# StLink.net
KiCad netlist of a schematic drawn in Altium Designer
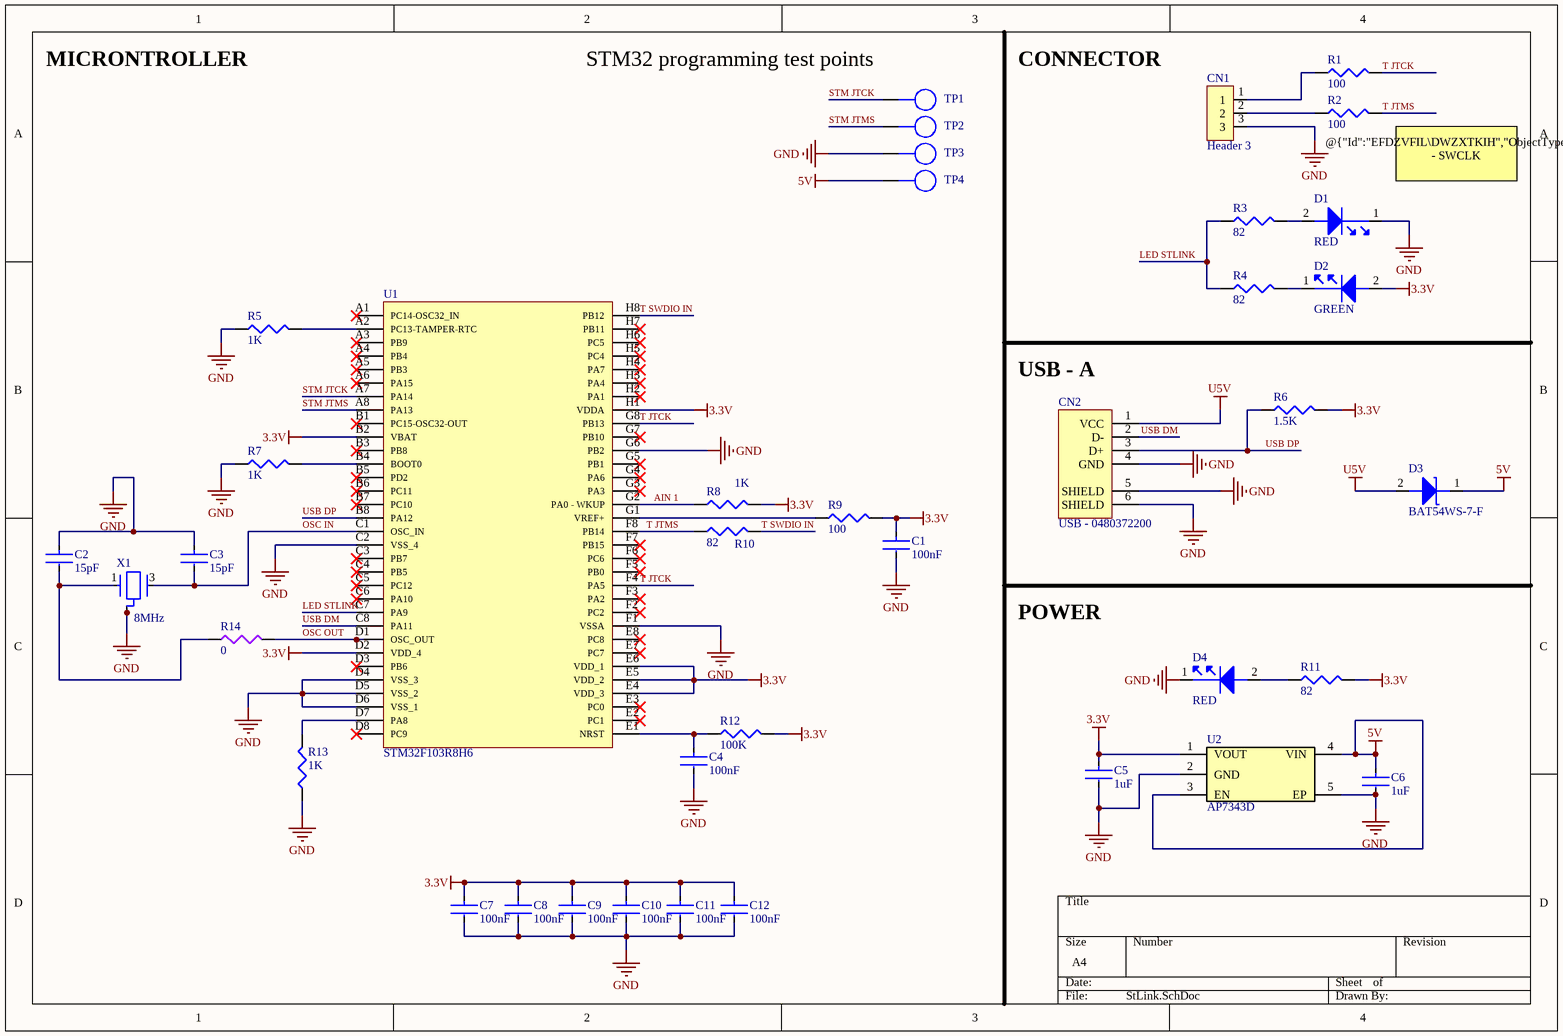
[diagram p0: StLink.SchDoc]

(export (version "E")
  (design (tool "Eeschema 10.0.6"))
  (components
    (comp (ref "C1")
      (value "100nF")
      (footprint "C0201")
      (description "6.3V 100nF X5R ±10% 0201 Multilayer Ceramic Capacitors MLCC - SMD/SMT ROHS")
      (fields
        (field (name "MANUFACTURER") "Murata")
        (field (name "MANUFACTURER PART NUMBER") "GRM033R60J104KE19D")
      )
      (libsource (lib "StLink") (part "GRM033R60J104KE19D"))
    )
    (comp (ref "C2")
      (value "15pF")
      (footprint "C0201")
      (description "25V 15pF C0G ±5% 0201 Multilayer Ceramic Capacitors MLCC - SMD/SMT ROHS")
      (fields
        (field (name "MANUFACTURER") "Murata")
        (field (name "MANUFACTURER PART NUMBER") "GRM0335C1E150JA01D")
      )
      (libsource (lib "StLink") (part "GRM0335C1E150JA01D"))
    )
    (comp (ref "C3")
      (value "15pF")
      (footprint "C0201")
      (description "25V 15pF C0G ±5% 0201 Multilayer Ceramic Capacitors MLCC - SMD/SMT ROHS")
      (fields
        (field (name "MANUFACTURER") "Murata")
        (field (name "MANUFACTURER PART NUMBER") "GRM0335C1E150JA01D")
      )
      (libsource (lib "StLink") (part "GRM0335C1E150JA01D"))
    )
    (comp (ref "C4")
      (value "100nF")
      (footprint "C0201")
      (description "6.3V 100nF X5R ±10% 0201 Multilayer Ceramic Capacitors MLCC - SMD/SMT ROHS")
      (fields
        (field (name "MANUFACTURER") "Murata")
        (field (name "MANUFACTURER PART NUMBER") "GRM033R60J104KE19D")
      )
      (libsource (lib "StLink") (part "GRM033R60J104KE19D"))
    )
    (comp (ref "C5")
      (value "1uF")
      (footprint "C0201")
      (description "16V 1uF X5R ±20% 0201 Multilayer Ceramic Capacitors MLCC - SMD/SMT ROHS")
      (fields
        (field (name "MANUFACTURER") "Murata")
        (field (name "MANUFACTURER PART NUMBER") "GRM033R61C105ME15D")
      )
      (libsource (lib "StLink") (part "GRM033R61C105ME15D"))
    )
    (comp (ref "C6")
      (value "1uF")
      (footprint "C0201")
      (description "16V 1uF X5R ±20% 0201 Multilayer Ceramic Capacitors MLCC - SMD/SMT ROHS")
      (fields
        (field (name "MANUFACTURER") "Murata")
        (field (name "MANUFACTURER PART NUMBER") "GRM033R61C105ME15D")
      )
      (libsource (lib "StLink") (part "GRM033R61C105ME15D"))
    )
    (comp (ref "C7")
      (value "100nF")
      (footprint "C0201")
      (description "6.3V 100nF X5R ±10% 0201 Multilayer Ceramic Capacitors MLCC - SMD/SMT ROHS")
      (fields
        (field (name "MANUFACTURER") "Murata")
        (field (name "MANUFACTURER PART NUMBER") "GRM033R60J104KE19D")
      )
      (libsource (lib "StLink") (part "GRM033R60J104KE19D"))
    )
    (comp (ref "C8")
      (value "100nF")
      (footprint "C0201")
      (description "6.3V 100nF X5R ±10% 0201 Multilayer Ceramic Capacitors MLCC - SMD/SMT ROHS")
      (fields
        (field (name "MANUFACTURER") "Murata")
        (field (name "MANUFACTURER PART NUMBER") "GRM033R60J104KE19D")
      )
      (libsource (lib "StLink") (part "GRM033R60J104KE19D"))
    )
    (comp (ref "C9")
      (value "100nF")
      (footprint "C0201")
      (description "6.3V 100nF X5R ±10% 0201 Multilayer Ceramic Capacitors MLCC - SMD/SMT ROHS")
      (fields
        (field (name "MANUFACTURER") "Murata")
        (field (name "MANUFACTURER PART NUMBER") "GRM033R60J104KE19D")
      )
      (libsource (lib "StLink") (part "GRM033R60J104KE19D"))
    )
    (comp (ref "C10")
      (value "100nF")
      (footprint "C0201")
      (description "6.3V 100nF X5R ±10% 0201 Multilayer Ceramic Capacitors MLCC - SMD/SMT ROHS")
      (fields
        (field (name "MANUFACTURER") "Murata")
        (field (name "MANUFACTURER PART NUMBER") "GRM033R60J104KE19D")
      )
      (libsource (lib "StLink") (part "GRM033R60J104KE19D"))
    )
    (comp (ref "C11")
      (value "100nF")
      (footprint "C0201")
      (description "6.3V 100nF X5R ±10% 0201 Multilayer Ceramic Capacitors MLCC - SMD/SMT ROHS")
      (fields
        (field (name "MANUFACTURER") "Murata")
        (field (name "MANUFACTURER PART NUMBER") "GRM033R60J104KE19D")
      )
      (libsource (lib "StLink") (part "GRM033R60J104KE19D"))
    )
    (comp (ref "C12")
      (value "100nF")
      (footprint "C0201")
      (description "6.3V 100nF X5R ±10% 0201 Multilayer Ceramic Capacitors MLCC - SMD/SMT ROHS")
      (fields
        (field (name "MANUFACTURER") "Murata")
        (field (name "MANUFACTURER PART NUMBER") "GRM033R60J104KE19D")
      )
      (libsource (lib "StLink") (part "GRM033R60J104KE19D"))
    )
    (comp (ref "CN1")
      (value "Header 3")
      (footprint "H3x1")
      (description "Conn Shrouded Header (4 Sides) HDR 3 POS 1mm Solder RA Side Entry SMD Micro Mate™ Bulk")
      (fields
        (field (name "MANUFACTURER") "Samtec")
        (field (name "MANUFACTURER PART NUMBER") "T1M-03-F-SH-L")
      )
      (libsource (lib "StLink") (part "T1M-03-F-SH-L"))
    )
    (comp (ref "CN2")
      (value "USB - 0480372200")
      (footprint "usb A")
      (description "USB Connector, 4 Contact(s), Male, Right Angle, Surface Mount Terminal, Locking, Plug")
      (fields (field (name "MANUFACTURER") "Molex") (field (name "MANUFACTURER PART NUMBER") "48037-2200"))
      (libsource (lib "StLink") (part "48037-2200"))
    )
    (comp (ref "D1")
      (value "RED")
      (footprint "Led 0402")
      (description "Wurth Elektronik LED, WL-SMCC, 1005 (0402), 625 nm, 1 x 0.5 x 0.4mm")
      (fields
        (field (name "MANUFACTURER") "Wurth Elektronik")
        (field (name "MANUFACTURER PART NUMBER") "150040RS73240")
      )
      (libsource (lib "StLink") (part "150040RS73240"))
    )
    (comp (ref "D2")
      (value "GREEN")
      (footprint "Led 0402")
      (description "Wurth Elektronik LED, WL-SMCC, 1005 (0402), 570 nm, 1 x 0.5 x 0.4mm")
      (fields
        (field (name "MANUFACTURER") "Wurth Elektronik")
        (field (name "MANUFACTURER PART NUMBER") "150040VS73240")
      )
      (libsource (lib "StLink") (part "150040VS73240"))
    )
    (comp (ref "D3")
      (value "BAT54WS-7-F")
      (footprint "SOD323")
      (description "Schottky Diode Sod323 T&r 3K Rohs Compliant: Yes ¦Diodes Inc. BAT54WS-7-F")
      (fields (field (name "MANUFACTURER") "Diodes Inc."))
      (libsource (lib "StLink") (part "BAT54WS-7-F"))
    )
    (comp (ref "D4")
      (value "RED")
      (footprint "Led 0402")
      (description "Wurth Elektronik LED, WL-SMCC, 1005 (0402), 625 nm, 1 x 0.5 x 0.4mm")
      (fields
        (field (name "MANUFACTURER") "Wurth Elektronik")
        (field (name "MANUFACTURER PART NUMBER") "150040RS73240")
      )
      (libsource (lib "StLink") (part "150040RS73240"))
    )
    (comp (ref "R1")
      (value "100")
      (footprint "R0201")
      (description "50mW Thick Film Resistors 25V ±1% ±200ppm/℃ 100Ω 0201 Chip Resistor - Surface Mount ROHS")
      (fields
        (field (name "MANUFACTURER") "Yageo Group")
        (field (name "MANUFACTURER PART NUMBER") "RC0201FR-07100RL")
      )
      (libsource (lib "StLink") (part "RC0201FR-07100RL"))
    )
    (comp (ref "R2")
      (value "100")
      (footprint "R0201")
      (description "50mW Thick Film Resistors 25V ±1% ±200ppm/℃ 100Ω 0201 Chip Resistor - Surface Mount ROHS")
      (fields
        (field (name "MANUFACTURER") "Yageo Group")
        (field (name "MANUFACTURER PART NUMBER") "RC0201FR-07100RL")
      )
      (libsource (lib "StLink") (part "RC0201FR-07100RL"))
    )
    (comp (ref "R3")
      (value "82")
      (footprint "R0201")
      (description "Res Thick Film 0201 82 Ohm 5% 0.05W(1/20W) ±200ppm/C Pad SMD T/R")
      (fields
        (field (name "MANUFACTURER") "Yageo Group")
        (field (name "MANUFACTURER PART NUMBER") "RC0201JR-0782RL")
      )
      (libsource (lib "StLink") (part "RC0201JR-0782RL"))
    )
    (comp (ref "R4")
      (value "82")
      (footprint "R0201")
      (description "Res Thick Film 0201 82 Ohm 5% 0.05W(1/20W) ±200ppm/C Pad SMD T/R")
      (fields
        (field (name "MANUFACTURER") "Yageo Group")
        (field (name "MANUFACTURER PART NUMBER") "RC0201JR-0782RL")
      )
      (libsource (lib "StLink") (part "RC0201JR-0782RL"))
    )
    (comp (ref "R5")
      (value "1K")
      (footprint "R0201")
      (description "Res Thick Film 0201 1K Ohm 1% 0.05W(1/20W) ±200ppm/C Pad SMD T/R")
      (fields
        (field (name "MANUFACTURER") "Yageo Group")
        (field (name "MANUFACTURER PART NUMBER") "RC0201FR-071KL")
      )
      (libsource (lib "StLink") (part "RC0201FR-071KL"))
    )
    (comp (ref "R6")
      (value "1.5K")
      (footprint "R0201")
      (description "Res Thick Film 0201 1.5K Ohm 5% 0.05W(1/20W) ±200ppm/C Pad SMD T/R")
      (fields
        (field (name "MANUFACTURER") "Yageo Group")
        (field (name "MANUFACTURER PART NUMBER") "RC0201JR-071K5L")
      )
      (libsource (lib "StLink") (part "RC0201JR-071K5L"))
    )
    (comp (ref "R7")
      (value "1K")
      (footprint "R0201")
      (description "Res Thick Film 0201 1K Ohm 1% 0.05W(1/20W) ±200ppm/C Pad SMD T/R")
      (fields
        (field (name "MANUFACTURER") "Yageo Group")
        (field (name "MANUFACTURER PART NUMBER") "RC0201FR-071KL")
      )
      (libsource (lib "StLink") (part "RC0201FR-071KL"))
    )
    (comp (ref "R8")
      (value "1K")
      (footprint "R0201")
      (description "Res Thick Film 0201 1K Ohm 1% 0.05W(1/20W) ±200ppm/C Pad SMD T/R")
      (fields
        (field (name "MANUFACTURER") "Yageo Group")
        (field (name "MANUFACTURER PART NUMBER") "RC0201FR-071KL")
      )
      (libsource (lib "StLink") (part "RC0201FR-071KL"))
    )
    (comp (ref "R9")
      (value "100")
      (footprint "R0201")
      (description "50mW Thick Film Resistors 25V ±1% ±200ppm/℃ 100Ω 0201 Chip Resistor - Surface Mount ROHS")
      (fields
        (field (name "MANUFACTURER") "Yageo Group")
        (field (name "MANUFACTURER PART NUMBER") "RC0201FR-07100RL")
      )
      (libsource (lib "StLink") (part "RC0201FR-07100RL"))
    )
    (comp (ref "R10")
      (value "82")
      (footprint "R0201")
      (description "Res Thick Film 0201 82 Ohm 5% 0.05W(1/20W) ±200ppm/C Pad SMD T/R")
      (fields
        (field (name "MANUFACTURER") "Yageo Group")
        (field (name "MANUFACTURER PART NUMBER") "RC0201JR-0782RL")
      )
      (libsource (lib "StLink") (part "RC0201JR-0782RL"))
    )
    (comp (ref "R11")
      (value "82")
      (footprint "R0201")
      (description "Res Thick Film 0201 82 Ohm 5% 0.05W(1/20W) ±200ppm/C Pad SMD T/R")
      (fields
        (field (name "MANUFACTURER") "Yageo Group")
        (field (name "MANUFACTURER PART NUMBER") "RC0201JR-0782RL")
      )
      (libsource (lib "StLink") (part "RC0201JR-0782RL"))
    )
    (comp (ref "R12")
      (value "100K")
      (footprint "R0201")
      (description "50mW Thick Film Resistors 25V ±1% ±200ppm/℃ 100kΩ 0201 Chip Resistor - Surface Mount ROHS")
      (fields
        (field (name "MANUFACTURER") "Yageo Group")
        (field (name "MANUFACTURER PART NUMBER") "RC0201FR-07100KL")
      )
      (libsource (lib "StLink") (part "RC0201FR-07100KL"))
    )
    (comp (ref "R13")
      (value "1K")
      (footprint "R0201")
      (description "Res Thick Film 0201 1K Ohm 1% 0.05W(1/20W) ±200ppm/C Pad SMD T/R")
      (fields
        (field (name "MANUFACTURER") "Yageo Group")
        (field (name "MANUFACTURER PART NUMBER") "RC0201FR-071KL")
      )
      (libsource (lib "StLink") (part "RC0201FR-071KL"))
    )
    (comp (ref "R14")
      (value "0")
      (footprint "R0201")
      (description "GENERAL PURPOSE CHIP RESISTOR Metal Glaze/thick Film, 0.05W, 0ohm, Surface Mount, 0201")
      (fields
        (field (name "MANUFACTURER") "Yageo Group")
        (field (name "MANUFACTURER PART NUMBER") "RC0201JR-070RL")
      )
      (libsource (lib "StLink") (part "RC0201JR-070RL"))
    )
    (comp (ref "TP1") (value "Test_Point") (footprint "PAD") (libsource (lib "StLink") (part "Test_Point")))
    (comp (ref "TP2") (value "Test_Point") (footprint "PAD") (libsource (lib "StLink") (part "Test_Point")))
    (comp (ref "TP3") (value "Test_Point") (footprint "PAD") (libsource (lib "StLink") (part "Test_Point")))
    (comp (ref "TP4") (value "Test_Point") (footprint "PAD") (libsource (lib "StLink") (part "Test_Point")))
    (comp (ref "U1")
      (value "STM32F103R8H6")
      (footprint "Micro BGA")
      (description "MCU 32-bit STM32F ARM Cortex M3 RISC 64KB Flash 2.5V/3.3V 64-Pin TFBGA Tray")
      (fields (field (name "MANUFACTURER") "STMicroelectronics"))
      (libsource (lib "StLink") (part "STM32F103R8H6"))
    )
    (comp (ref "U2")
      (value "AP7343D")
      (footprint "AP7343D")
      (description "Ldo, Fixed, 3.3V, 0.3A, -40 To 85Deg C Rohs Compliant: Yes ¦Diodes Inc. AP7343D-33FS4-7B")
      (fields
        (field (name "MANUFACTURER") "Diodes Inc.")
        (field (name "MANUFACTURER PART NUMBER") "AP7343D-33FS4-7B")
      )
      (libsource (lib "StLink") (part "AP7343D-33FS4-7B"))
    )
    (comp (ref "X1")
      (value "8MHz")
      (footprint "Cristal ECS")
      (description "Crystal 8MHz ±20ppm (Tol) ±30ppm (Stability) 12pF FUND 400Ohm 4-Pin Mini-CSMD T/R")
      (fields
        (field (name "MANUFACTURER") "ECS International")
        (field (name "MANUFACTURER PART NUMBER") "ECS-80-12-33-JGN-TR")
      )
      (libsource (lib "StLink") (part "ECS-80-12-33-JGN-TR"))
    )
  )
  (nets
    (net (code "2") (name "/AIN 1") (class "Default")
      (node (ref "R8") (pin "1") (pinfunction "1_1") (pintype "passive"))
      (node (ref "U1") (pin "G2") (pinfunction "PA0_-_WKUP_G2") (pintype "passive"))
    )
    (net (code "3") (name "/LED STLINK") (class "Default")
      (node (ref "R3") (pin "1") (pinfunction "1_1") (pintype "passive"))
      (node (ref "R4") (pin "1") (pinfunction "1_1") (pintype "passive"))
      (node (ref "U1") (pin "C7") (pinfunction "PA9_C7") (pintype "passive"))
    )
    (net (code "4") (name "/OSC IN") (class "Default")
      (node (ref "C3") (pin "2") (pinfunction "2_2") (pintype "passive"))
      (node (ref "U1") (pin "C1") (pinfunction "OSC_IN_C1") (pintype "passive"))
      (node (ref "X1") (pin "3") (pinfunction "3_3") (pintype "passive"))
    )
    (net (code "5") (name "/OSC OUT") (class "Default")
      (node (ref "R14") (pin "2") (pinfunction "2_2") (pintype "passive"))
      (node (ref "U1") (pin "D1") (pinfunction "OSC_OUT_D1") (pintype "passive"))
    )
    (net (code "6") (name "/STM JTCK") (class "Default")
      (node (ref "TP1") (pin "1") (pinfunction "1_1") (pintype "passive"))
      (node (ref "U1") (pin "A7") (pinfunction "PA14_A7") (pintype "passive"))
    )
    (net (code "7") (name "/STM JTMS") (class "Default")
      (node (ref "TP2") (pin "1") (pinfunction "1_1") (pintype "passive"))
      (node (ref "U1") (pin "A8") (pinfunction "PA13_A8") (pintype "passive"))
    )
    (net (code "8") (name "/T JTCK") (class "Default")
      (node (ref "R1") (pin "2") (pinfunction "2_2") (pintype "passive"))
      (node (ref "U1") (pin "F4") (pinfunction "PA5_F4") (pintype "passive"))
      (node (ref "U1") (pin "G8") (pinfunction "PB13_G8") (pintype "passive"))
    )
    (net (code "9") (name "/T JTMS") (class "Default")
      (node (ref "R10") (pin "1") (pinfunction "1_1") (pintype "passive"))
      (node (ref "R2") (pin "2") (pinfunction "2_2") (pintype "passive"))
      (node (ref "U1") (pin "F8") (pinfunction "PB14_F8") (pintype "passive"))
    )
    (net (code "10") (name "/T SWDIO IN") (class "Default")
      (node (ref "R10") (pin "2") (pinfunction "2_2") (pintype "passive"))
      (node (ref "U1") (pin "H8") (pinfunction "PB12_H8") (pintype "passive"))
    )
    (net (code "11") (name "/USB DM") (class "Default")
      (node (ref "CN2") (pin "2") (pinfunction "D-_2") (pintype "passive"))
      (node (ref "U1") (pin "C8") (pinfunction "PA11_C8") (pintype "passive"))
    )
    (net (code "12") (name "/USB DP") (class "Default")
      (node (ref "CN2") (pin "3") (pinfunction "D+_3") (pintype "passive"))
      (node (ref "R6") (pin "1") (pinfunction "1_1") (pintype "passive"))
      (node (ref "U1") (pin "B8") (pinfunction "PA12_B8") (pintype "passive"))
    )
    (net (code "13") (name "3.3V") (class "Default")
      (node (ref "C1") (pin "1") (pinfunction "1_1") (pintype "passive"))
      (node (ref "C10") (pin "1") (pinfunction "1_1") (pintype "passive"))
      (node (ref "C11") (pin "1") (pinfunction "1_1") (pintype "passive"))
      (node (ref "C12") (pin "1") (pinfunction "1_1") (pintype "passive"))
      (node (ref "C5") (pin "1") (pinfunction "1_1") (pintype "passive"))
      (node (ref "C7") (pin "1") (pinfunction "1_1") (pintype "passive"))
      (node (ref "C8") (pin "1") (pinfunction "1_1") (pintype "passive"))
      (node (ref "C9") (pin "1") (pinfunction "1_1") (pintype "passive"))
      (node (ref "D2") (pin "2") (pinfunction "2_2") (pintype "passive"))
      (node (ref "R11") (pin "2") (pinfunction "2_2") (pintype "passive"))
      (node (ref "R12") (pin "2") (pinfunction "2_2") (pintype "passive"))
      (node (ref "R6") (pin "2") (pinfunction "2_2") (pintype "passive"))
      (node (ref "R8") (pin "2") (pinfunction "2_2") (pintype "passive"))
      (node (ref "R9") (pin "2") (pinfunction "2_2") (pintype "passive"))
      (node (ref "U1") (pin "B2") (pinfunction "VBAT_B2") (pintype "passive"))
      (node (ref "U1") (pin "D2") (pinfunction "VDD_4_D2") (pintype "passive"))
      (node (ref "U1") (pin "E4") (pinfunction "VDD_3_E4") (pintype "passive"))
      (node (ref "U1") (pin "E5") (pinfunction "VDD_2_E5") (pintype "passive"))
      (node (ref "U1") (pin "E6") (pinfunction "VDD_1_E6") (pintype "passive"))
      (node (ref "U1") (pin "H1") (pinfunction "VDDA_H1") (pintype "passive"))
      (node (ref "U2") (pin "1") (pinfunction "VOUT_1") (pintype "passive"))
    )
    (net (code "14") (name "5V") (class "Default")
      (node (ref "C6") (pin "1") (pinfunction "1_1") (pintype "passive"))
      (node (ref "D3") (pin "1") (pinfunction "1_1") (pintype "passive"))
      (node (ref "TP4") (pin "1") (pinfunction "1_1") (pintype "passive"))
      (node (ref "U2") (pin "3") (pinfunction "EN_3") (pintype "passive"))
      (node (ref "U2") (pin "4") (pinfunction "VIN_4") (pintype "passive"))
    )
    (net (code "15") (name "GND") (class "Default")
      (node (ref "C1") (pin "2") (pinfunction "2_2") (pintype "passive"))
      (node (ref "C10") (pin "2") (pinfunction "2_2") (pintype "passive"))
      (node (ref "C11") (pin "2") (pinfunction "2_2") (pintype "passive"))
      (node (ref "C12") (pin "2") (pinfunction "2_2") (pintype "passive"))
      (node (ref "C2") (pin "1") (pinfunction "1_1") (pintype "passive"))
      (node (ref "C3") (pin "1") (pinfunction "1_1") (pintype "passive"))
      (node (ref "C4") (pin "2") (pinfunction "2_2") (pintype "passive"))
      (node (ref "C5") (pin "2") (pinfunction "2_2") (pintype "passive"))
      (node (ref "C6") (pin "2") (pinfunction "2_2") (pintype "passive"))
      (node (ref "C7") (pin "2") (pinfunction "2_2") (pintype "passive"))
      (node (ref "C8") (pin "2") (pinfunction "2_2") (pintype "passive"))
      (node (ref "C9") (pin "2") (pinfunction "2_2") (pintype "passive"))
      (node (ref "CN1") (pin "3") (pinfunction "3_3") (pintype "passive"))
      (node (ref "CN2") (pin "4") (pinfunction "GND_4") (pintype "passive"))
      (node (ref "CN2") (pin "5") (pinfunction "SHIELD_5") (pintype "passive"))
      (node (ref "CN2") (pin "6") (pinfunction "SHIELD_6") (pintype "passive"))
      (node (ref "D1") (pin "1") (pinfunction "1_1") (pintype "passive"))
      (node (ref "D4") (pin "1") (pinfunction "1_1") (pintype "passive"))
      (node (ref "R13") (pin "1") (pinfunction "1_1") (pintype "passive"))
      (node (ref "R5") (pin "1") (pinfunction "1_1") (pintype "passive"))
      (node (ref "R7") (pin "1") (pinfunction "1_1") (pintype "passive"))
      (node (ref "TP3") (pin "1") (pinfunction "1_1") (pintype "passive"))
      (node (ref "U1") (pin "C2") (pinfunction "VSS_4_C2") (pintype "passive"))
      (node (ref "U1") (pin "D4") (pinfunction "VSS_3_D4") (pintype "passive"))
      (node (ref "U1") (pin "D5") (pinfunction "VSS_2_D5") (pintype "passive"))
      (node (ref "U1") (pin "D6") (pinfunction "VSS_1_D6") (pintype "passive"))
      (node (ref "U1") (pin "F1") (pinfunction "VSSA_F1") (pintype "passive"))
      (node (ref "U1") (pin "G6") (pinfunction "PB2_G6") (pintype "passive"))
      (node (ref "U2") (pin "2") (pinfunction "GND_2") (pintype "passive"))
      (node (ref "U2") (pin "5") (pinfunction "EP_5") (pintype "passive"))
      (node (ref "X1") (pin "2") (pinfunction "GND_2") (pintype "passive"))
      (node (ref "X1") (pin "4") (pinfunction "GND_4") (pintype "passive"))
    )
    (net (code "16") (name "Net-(C2-Pad2)") (class "Default")
      (node (ref "C2") (pin "2") (pinfunction "2_2") (pintype "passive"))
      (node (ref "R14") (pin "1") (pinfunction "1_1") (pintype "passive"))
      (node (ref "X1") (pin "1") (pinfunction "1_1") (pintype "passive"))
    )
    (net (code "17") (name "Net-(CN1-Pad1)") (class "Default")
      (node (ref "CN1") (pin "1") (pinfunction "1_1") (pintype "passive"))
      (node (ref "R1") (pin "1") (pinfunction "1_1") (pintype "passive"))
    )
    (net (code "18") (name "Net-(CN1-Pad2)") (class "Default")
      (node (ref "CN1") (pin "2") (pinfunction "2_2") (pintype "passive"))
      (node (ref "R2") (pin "1") (pinfunction "1_1") (pintype "passive"))
    )
    (net (code "19") (name "Net-(D1-Pad2)") (class "Default")
      (node (ref "D1") (pin "2") (pinfunction "2_2") (pintype "passive"))
      (node (ref "R3") (pin "2") (pinfunction "2_2") (pintype "passive"))
    )
    (net (code "20") (name "Net-(D2-Pad1)") (class "Default")
      (node (ref "D2") (pin "1") (pinfunction "1_1") (pintype "passive"))
      (node (ref "R4") (pin "2") (pinfunction "2_2") (pintype "passive"))
    )
    (net (code "21") (name "Net-(D4-Pad2)") (class "Default")
      (node (ref "D4") (pin "2") (pinfunction "2_2") (pintype "passive"))
      (node (ref "R11") (pin "1") (pinfunction "1_1") (pintype "passive"))
    )
    (net (code "22") (name "Net-(U1-BOOT0)") (class "Default")
      (node (ref "R7") (pin "2") (pinfunction "2_2") (pintype "passive"))
      (node (ref "U1") (pin "B4") (pinfunction "BOOT0_B4") (pintype "passive"))
    )
    (net (code "23") (name "Net-(U1-NRST)") (class "Default")
      (node (ref "C4") (pin "1") (pinfunction "1_1") (pintype "passive"))
      (node (ref "R12") (pin "1") (pinfunction "1_1") (pintype "passive"))
      (node (ref "U1") (pin "E1") (pinfunction "NRST_E1") (pintype "passive"))
    )
    (net (code "24") (name "Net-(U1-PA8)") (class "Default")
      (node (ref "R13") (pin "2") (pinfunction "2_2") (pintype "passive"))
      (node (ref "U1") (pin "D7") (pinfunction "PA8_D7") (pintype "passive"))
    )
    (net (code "25") (name "Net-(U1-PC13-TAMPER-RTC)") (class "Default")
      (node (ref "R5") (pin "2") (pinfunction "2_2") (pintype "passive"))
      (node (ref "U1") (pin "A2") (pinfunction "PC13-TAMPER-RTC_A2") (pintype "passive"))
    )
    (net (code "26") (name "Net-(U1-VREF+)") (class "Default")
      (node (ref "R9") (pin "1") (pinfunction "1_1") (pintype "passive"))
      (node (ref "U1") (pin "G1") (pinfunction "VREF+_G1") (pintype "passive"))
    )
    (net (code "27") (name "U5V") (class "Default")
      (node (ref "CN2") (pin "1") (pinfunction "VCC_1") (pintype "passive"))
      (node (ref "D3") (pin "2") (pinfunction "2_2") (pintype "passive"))
    )
    (net (code "28") (name "unconnected-(U1-PA1-PadH2)") (class "Default")
      (node (ref "U1") (pin "H2") (pinfunction "PA1_H2") (pintype "passive+no_connect"))
    )
    (net (code "29") (name "unconnected-(U1-PA2-PadF3)") (class "Default")
      (node (ref "U1") (pin "F3") (pinfunction "PA2_F3") (pintype "passive+no_connect"))
    )
    (net (code "30") (name "unconnected-(U1-PA3-PadG3)") (class "Default")
      (node (ref "U1") (pin "G3") (pinfunction "PA3_G3") (pintype "passive+no_connect"))
    )
    (net (code "31") (name "unconnected-(U1-PA4-PadH3)") (class "Default")
      (node (ref "U1") (pin "H3") (pinfunction "PA4_H3") (pintype "passive+no_connect"))
    )
    (net (code "32") (name "unconnected-(U1-PA6-PadG4)") (class "Default")
      (node (ref "U1") (pin "G4") (pinfunction "PA6_G4") (pintype "passive+no_connect"))
    )
    (net (code "33") (name "unconnected-(U1-PA7-PadH4)") (class "Default")
      (node (ref "U1") (pin "H4") (pinfunction "PA7_H4") (pintype "passive+no_connect"))
    )
    (net (code "34") (name "unconnected-(U1-PA10-PadC6)") (class "Default")
      (node (ref "U1") (pin "C6") (pinfunction "PA10_C6") (pintype "passive+no_connect"))
    )
    (net (code "35") (name "unconnected-(U1-PA15-PadA6)") (class "Default")
      (node (ref "U1") (pin "A6") (pinfunction "PA15_A6") (pintype "passive+no_connect"))
    )
    (net (code "36") (name "unconnected-(U1-PB0-PadF5)") (class "Default")
      (node (ref "U1") (pin "F5") (pinfunction "PB0_F5") (pintype "passive+no_connect"))
    )
    (net (code "37") (name "unconnected-(U1-PB1-PadG5)") (class "Default")
      (node (ref "U1") (pin "G5") (pinfunction "PB1_G5") (pintype "passive+no_connect"))
    )
    (net (code "38") (name "unconnected-(U1-PB3-PadA5)") (class "Default")
      (node (ref "U1") (pin "A5") (pinfunction "PB3_A5") (pintype "passive+no_connect"))
    )
    (net (code "39") (name "unconnected-(U1-PB4-PadA4)") (class "Default")
      (node (ref "U1") (pin "A4") (pinfunction "PB4_A4") (pintype "passive+no_connect"))
    )
    (net (code "40") (name "unconnected-(U1-PB5-PadC4)") (class "Default")
      (node (ref "U1") (pin "C4") (pinfunction "PB5_C4") (pintype "passive+no_connect"))
    )
    (net (code "41") (name "unconnected-(U1-PB6-PadD3)") (class "Default")
      (node (ref "U1") (pin "D3") (pinfunction "PB6_D3") (pintype "passive+no_connect"))
    )
    (net (code "42") (name "unconnected-(U1-PB7-PadC3)") (class "Default")
      (node (ref "U1") (pin "C3") (pinfunction "PB7_C3") (pintype "passive+no_connect"))
    )
    (net (code "43") (name "unconnected-(U1-PB8-PadB3)") (class "Default")
      (node (ref "U1") (pin "B3") (pinfunction "PB8_B3") (pintype "passive+no_connect"))
    )
    (net (code "44") (name "unconnected-(U1-PB9-PadA3)") (class "Default")
      (node (ref "U1") (pin "A3") (pinfunction "PB9_A3") (pintype "passive+no_connect"))
    )
    (net (code "45") (name "unconnected-(U1-PB10-PadG7)") (class "Default")
      (node (ref "U1") (pin "G7") (pinfunction "PB10_G7") (pintype "passive+no_connect"))
    )
    (net (code "46") (name "unconnected-(U1-PB11-PadH7)") (class "Default")
      (node (ref "U1") (pin "H7") (pinfunction "PB11_H7") (pintype "passive+no_connect"))
    )
    (net (code "47") (name "unconnected-(U1-PB15-PadF7)") (class "Default")
      (node (ref "U1") (pin "F7") (pinfunction "PB15_F7") (pintype "passive+no_connect"))
    )
    (net (code "48") (name "unconnected-(U1-PC0-PadE3)") (class "Default")
      (node (ref "U1") (pin "E3") (pinfunction "PC0_E3") (pintype "passive+no_connect"))
    )
    (net (code "49") (name "unconnected-(U1-PC1-PadE2)") (class "Default")
      (node (ref "U1") (pin "E2") (pinfunction "PC1_E2") (pintype "passive+no_connect"))
    )
    (net (code "50") (name "unconnected-(U1-PC2-PadF2)") (class "Default")
      (node (ref "U1") (pin "F2") (pinfunction "PC2_F2") (pintype "passive+no_connect"))
    )
    (net (code "51") (name "unconnected-(U1-PC4-PadH5)") (class "Default")
      (node (ref "U1") (pin "H5") (pinfunction "PC4_H5") (pintype "passive+no_connect"))
    )
    (net (code "52") (name "unconnected-(U1-PC5-PadH6)") (class "Default")
      (node (ref "U1") (pin "H6") (pinfunction "PC5_H6") (pintype "passive+no_connect"))
    )
    (net (code "53") (name "unconnected-(U1-PC6-PadF6)") (class "Default")
      (node (ref "U1") (pin "F6") (pinfunction "PC6_F6") (pintype "passive+no_connect"))
    )
    (net (code "54") (name "unconnected-(U1-PC7-PadE7)") (class "Default")
      (node (ref "U1") (pin "E7") (pinfunction "PC7_E7") (pintype "passive+no_connect"))
    )
    (net (code "55") (name "unconnected-(U1-PC8-PadE8)") (class "Default")
      (node (ref "U1") (pin "E8") (pinfunction "PC8_E8") (pintype "passive+no_connect"))
    )
    (net (code "56") (name "unconnected-(U1-PC9-PadD8)") (class "Default")
      (node (ref "U1") (pin "D8") (pinfunction "PC9_D8") (pintype "passive+no_connect"))
    )
    (net (code "57") (name "unconnected-(U1-PC10-PadB7)") (class "Default")
      (node (ref "U1") (pin "B7") (pinfunction "PC10_B7") (pintype "passive+no_connect"))
    )
    (net (code "58") (name "unconnected-(U1-PC11-PadB6)") (class "Default")
      (node (ref "U1") (pin "B6") (pinfunction "PC11_B6") (pintype "passive+no_connect"))
    )
    (net (code "59") (name "unconnected-(U1-PC12-PadC5)") (class "Default")
      (node (ref "U1") (pin "C5") (pinfunction "PC12_C5") (pintype "passive+no_connect"))
    )
    (net (code "60") (name "unconnected-(U1-PC14-OSC32_IN-PadA1)") (class "Default")
      (node (ref "U1") (pin "A1") (pinfunction "PC14-OSC32_IN_A1") (pintype "passive+no_connect"))
    )
    (net (code "61") (name "unconnected-(U1-PC15-OSC32-OUT-PadB1)") (class "Default")
      (node (ref "U1") (pin "B1") (pinfunction "PC15-OSC32-OUT_B1") (pintype "passive+no_connect"))
    )
    (net (code "62") (name "unconnected-(U1-PD2-PadB5)") (class "Default")
      (node (ref "U1") (pin "B5") (pinfunction "PD2_B5") (pintype "passive+no_connect"))
    )
  )
)
